# SCH_Esp32-LED-board_2025-09-09.net
KiCad netlist of a schematic drawn in EasyEDA
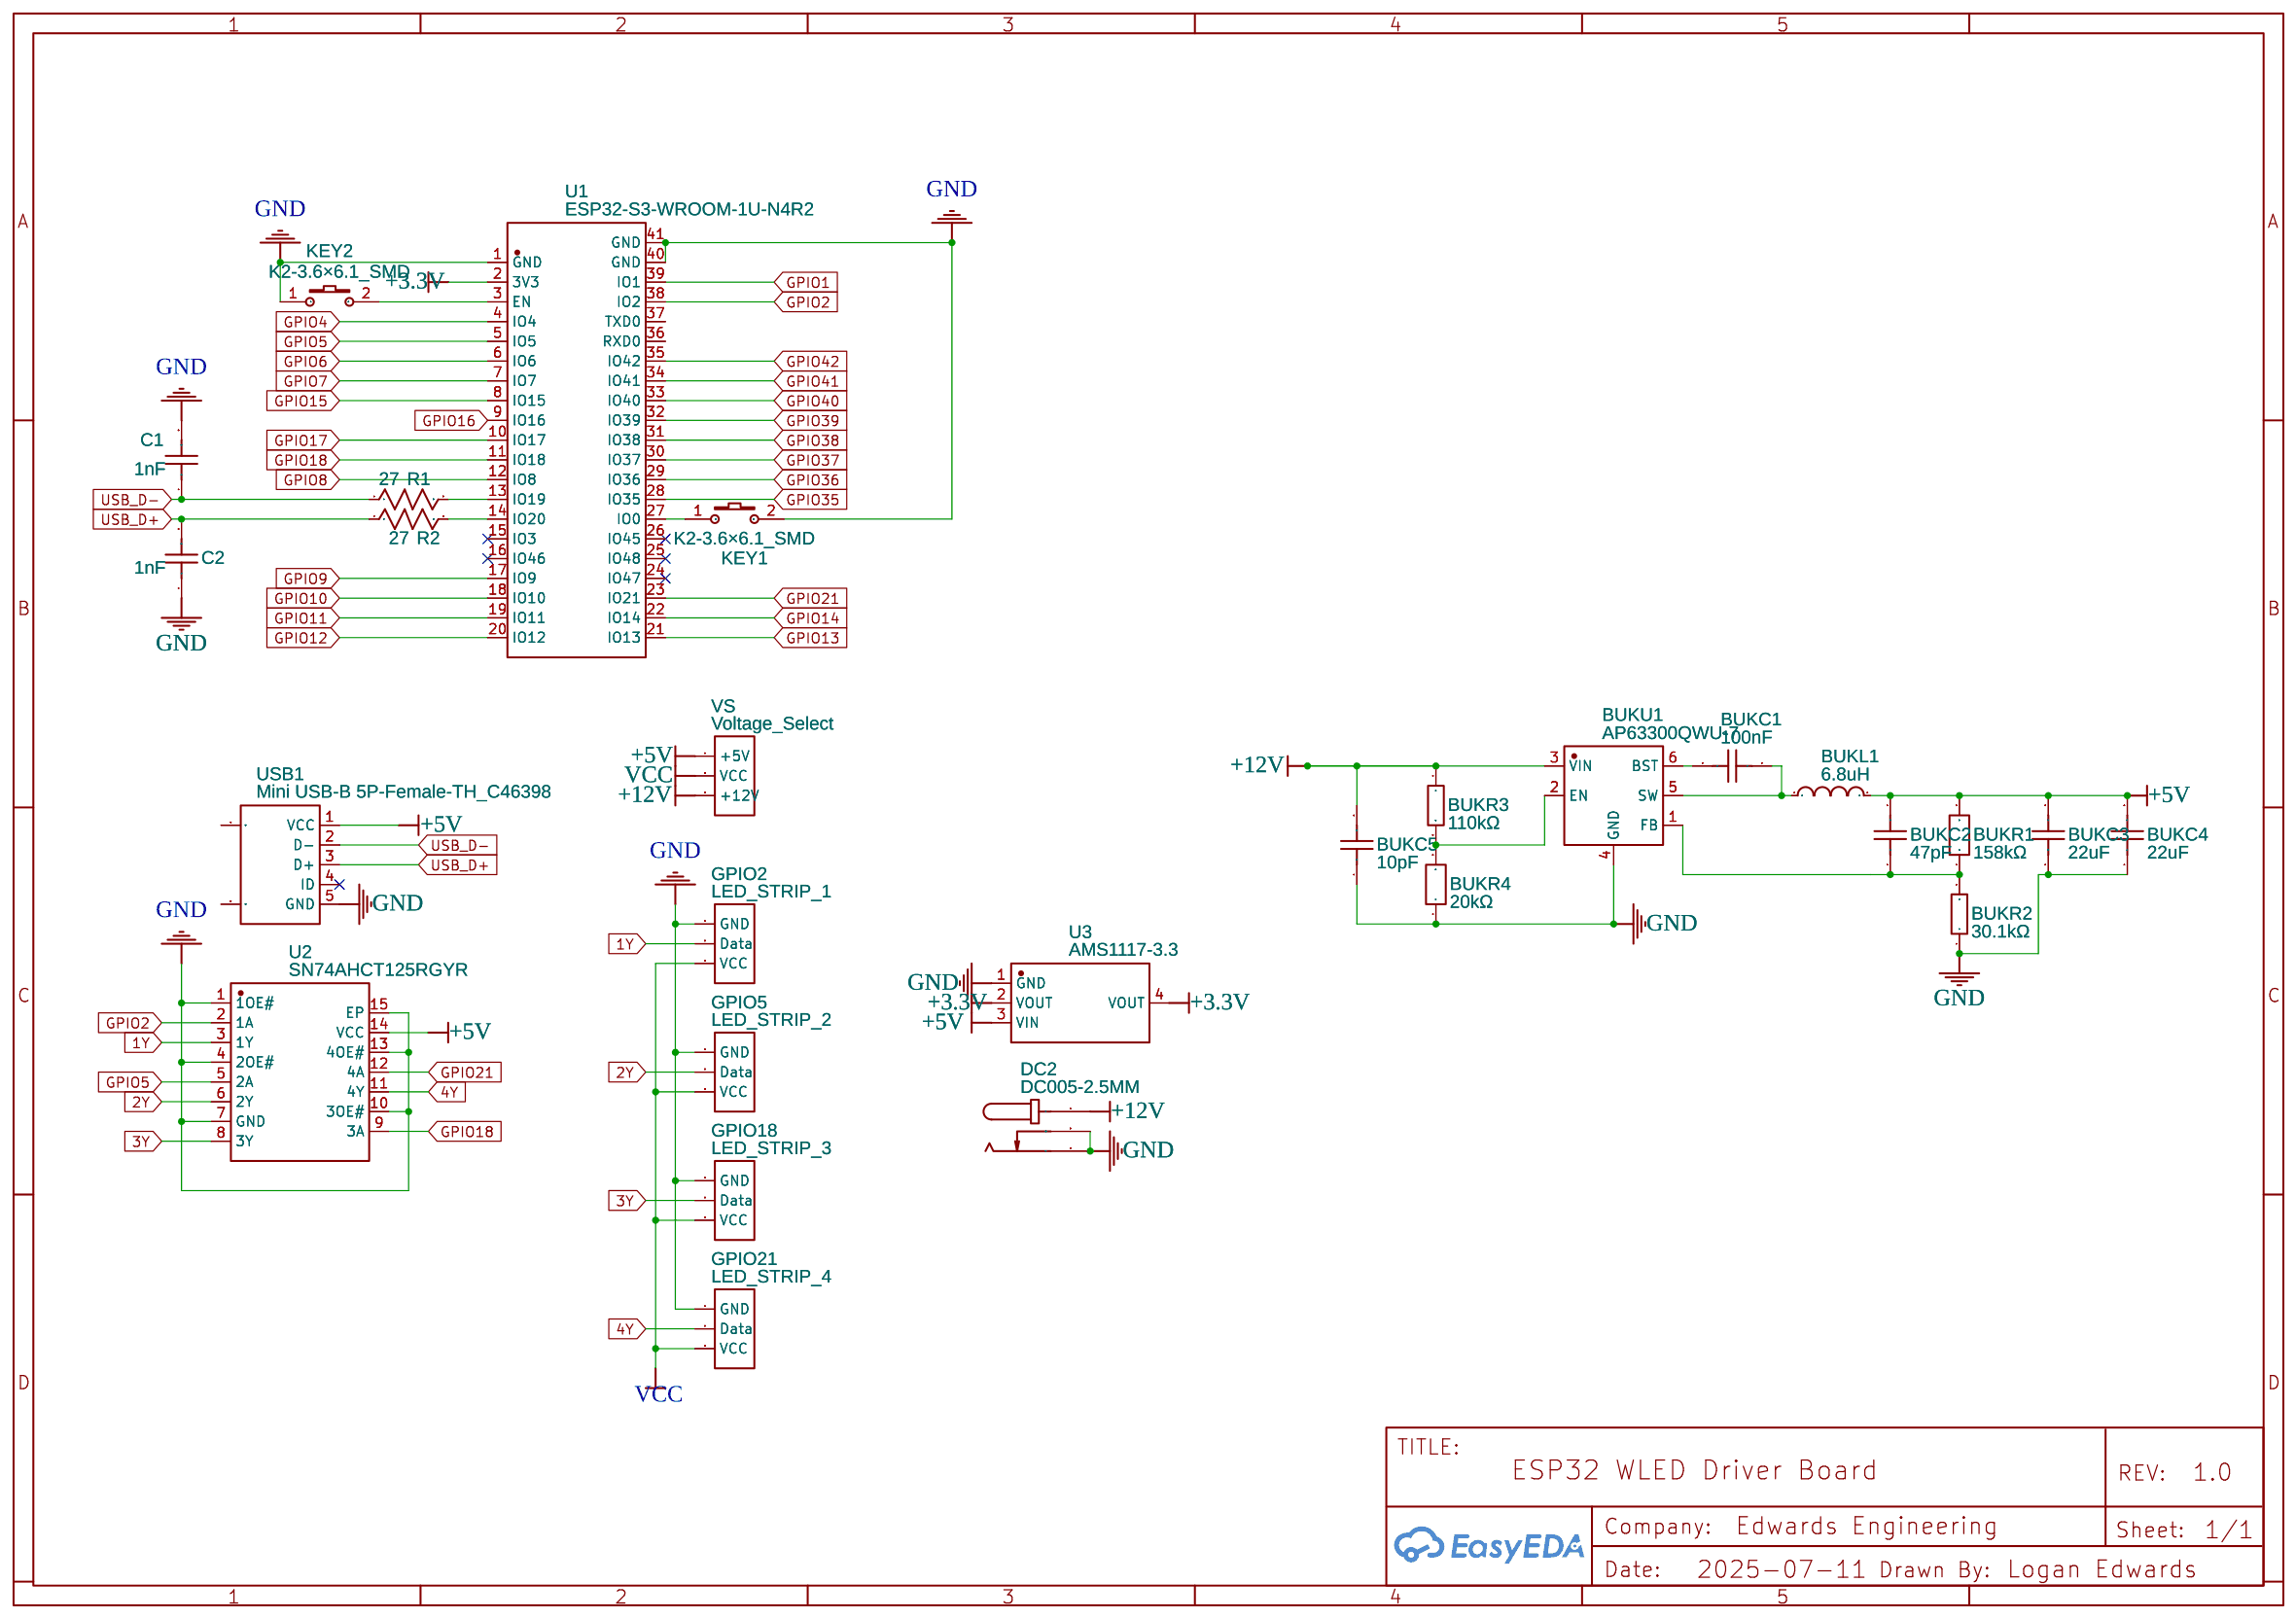
[diagram p0: schematic sheet]

(export (version "E")
  (design (tool "Eeschema 10.0.6"))
  (components
    (comp (ref "BUKC1")
      (value "100nF")
      (fields (field (name "Manufacturer Part") "0603B104J250NT") (field (name "Manufacturer") "FH(风华)"))
      (libsource (lib "") (part "0603B104J250NT"))
    )
    (comp (ref "BUKC2")
      (value "47pF")
      (fields
        (field (name "Manufacturer Part") "0603C0G470J500NT")
        (field (name "Manufacturer") "AIDE(爱迪电容)")
      )
      (libsource (lib "") (part "0603C0G470J500NT"))
    )
    (comp (ref "BUKC3")
      (value "22uF")
      (fields
        (field (name "Manufacturer Part") "HGC0603R5226M160NTHJ")
        (field (name "Manufacturer") "Chinocera(华瓷)")
      )
      (libsource (lib "") (part "HGC0603R5226M160NTHJ"))
    )
    (comp (ref "BUKC4")
      (value "22uF")
      (fields
        (field (name "Manufacturer Part") "HGC0603R5226M160NTHJ")
        (field (name "Manufacturer") "Chinocera(华瓷)")
      )
      (libsource (lib "") (part "HGC0603R5226M160NTHJ"))
    )
    (comp (ref "BUKC5")
      (value "10pF")
      (fields
        (field (name "Manufacturer Part") "CC0603FRNPO0BN100")
        (field (name "Manufacturer") "YAGEO(国巨)")
      )
      (libsource (lib "") (part "CC0603FRNPO0BN100"))
    )
    (comp (ref "BUKL1")
      (value "6.8uH")
      (fields (field (name "Manufacturer Part") "CMP160808JE6R8MT") (field (name "Manufacturer") "FH(风华)"))
      (libsource (lib "") (part "CMP160808JE6R8MT"))
    )
    (comp (ref "BUKR1")
      (value "158kΩ")
      (fields (field (name "Manufacturer Part") "FRC0603F1583TS") (field (name "Manufacturer") "FOJAN(富捷)"))
      (libsource (lib "") (part "FRC0603F1583TS"))
    )
    (comp (ref "BUKR2")
      (value "30.1kΩ")
      (fields
        (field (name "Manufacturer Part") "RMC060330.1K1%N")
        (field (name "Manufacturer") "Tyohm(幸亚电阻)")
      )
      (libsource (lib "") (part "RMC060330.1K1%N"))
    )
    (comp (ref "BUKR3")
      (value "110kΩ")
      (fields (field (name "Manufacturer Part") "RT0603BRD07110KL") (field (name "Manufacturer") "YAGEO(国巨)"))
      (libsource (lib "") (part "RT0603BRD07110KL"))
    )
    (comp (ref "BUKR4")
      (value "20kΩ")
      (fields (field (name "Manufacturer Part") "RT0603CRE0720KL") (field (name "Manufacturer") "YAGEO(国巨)"))
      (libsource (lib "") (part "RT0603CRE0720KL"))
    )
    (comp (ref "BUKU1")
      (value "AP63300QWU-7")
      (fields (field (name "Manufacturer") "DIODES(美台)"))
      (libsource (lib "") (part "AP63300QWU-7"))
    )
    (comp (ref "C1")
      (value "1nF")
      (fields
        (field (name "Manufacturer Part") "CL10B102KB8NNNC")
        (field (name "Manufacturer") "Samsung Electro-Mechanics")
      )
      (libsource (lib "") (part "C_0603_US"))
    )
    (comp (ref "C2")
      (value "1nF")
      (fields
        (field (name "Manufacturer Part") "CL10B102KB8NNNC")
        (field (name "Manufacturer") "Samsung Electro-Mechanics")
      )
      (libsource (lib "") (part "C_0603_US"))
    )
    (comp (ref "DC2")
      (value "DC005-2.5MM")
      (fields (field (name "Manufacturer Part") "DC005-T25") (field (name "Manufacturer") "SOFNG(硕方)"))
      (libsource (lib "") (part "DC005-2.5MM"))
    )
    (comp (ref "GPIO2")
      (value "LED_STRIP_1")
      (fields (field (name "Manufacturer Part") "2.54-1*3P针") (field (name "Manufacturer") "BOOMELE(博穆精密)"))
      (libsource (lib "") (part "Header-Male-2.54_1x3"))
    )
    (comp (ref "GPIO5")
      (value "LED_STRIP_2")
      (fields (field (name "Manufacturer Part") "2.54-1*3P针") (field (name "Manufacturer") "BOOMELE(博穆精密)"))
      (libsource (lib "") (part "Header-Male-2.54_1x3"))
    )
    (comp (ref "GPIO18")
      (value "LED_STRIP_3")
      (fields (field (name "Manufacturer Part") "2.54-1*3P针") (field (name "Manufacturer") "BOOMELE(博穆精密)"))
      (libsource (lib "") (part "Header-Male-2.54_1x3"))
    )
    (comp (ref "GPIO21")
      (value "LED_STRIP_4")
      (fields (field (name "Manufacturer Part") "2.54-1*3P针") (field (name "Manufacturer") "BOOMELE(博穆精密)"))
      (libsource (lib "") (part "Header-Male-2.54_1x3"))
    )
    (comp (ref "KEY1")
      (value "K2-3.6×6.1_SMD")
      (fields (field (name "Manufacturer Part") "K2-1107ST-A4SW-06"))
      (libsource (lib "") (part "K2-3.6×6.1_SMD"))
    )
    (comp (ref "KEY2")
      (value "K2-3.6×6.1_SMD")
      (fields (field (name "Manufacturer Part") "K2-1107ST-A4SW-06"))
      (libsource (lib "") (part "K2-3.6×6.1_SMD"))
    )
    (comp (ref "R1")
      (value "27")
      (fields
        (field (name "Manufacturer Part") "0603WAF270JT5E")
        (field (name "Manufacturer") "UNI-ROYAL(Uniroyal Elec)")
      )
      (libsource (lib "") (part "R_0603_US"))
    )
    (comp (ref "R2")
      (value "27")
      (fields
        (field (name "Manufacturer Part") "0603WAF270JT5E")
        (field (name "Manufacturer") "UNI-ROYAL(Uniroyal Elec)")
      )
      (libsource (lib "") (part "R_0603_US"))
    )
    (comp (ref "U1")
      (value "ESP32-S3-WROOM-1U-N4R2")
      (fields (field (name "Manufacturer") "ESPRESSIF(乐鑫)"))
      (libsource (lib "") (part "ESP32-S3-WROOM-1U-N4R2"))
    )
    (comp (ref "U2")
      (value "SN74AHCT125RGYR")
      (fields (field (name "Manufacturer") "TI(德州仪器)"))
      (libsource (lib "") (part "SN74AHCT125RGYR"))
    )
    (comp (ref "U3")
      (value "AMS1117-3.3")
      (fields (field (name "Manufacturer") "AMS"))
      (libsource (lib "") (part "AMS1117-3.3"))
    )
    (comp (ref "USB1")
      (value "Mini USB-B 5P-Female-TH_C46398")
      (fields (field (name "Manufacturer Part") "920-462A2021D10102") (field (name "Manufacturer") "精拓金"))
      (libsource (lib "") (part "Mini USB-B 5P-Female-TH_C46398"))
    )
    (comp (ref "VS")
      (value "Voltage_Select")
      (fields (field (name "Manufacturer Part") "2.54-1*3P针") (field (name "Manufacturer") "BOOMELE(博穆精密)"))
      (libsource (lib "") (part "Header-Male-2.54_1x3_1"))
    )
  )
  (nets
    (net (code "1") (name "+3.3V") (class "Default")
      (node (ref "U1") (pin "2") (pinfunction "3V3_2") (pintype "unspecified"))
      (node (ref "U3") (pin "2") (pinfunction "VOUT_2") (pintype "unspecified"))
      (node (ref "U3") (pin "4") (pinfunction "VOUT_4") (pintype "unspecified"))
    )
    (net (code "2") (name "+5V") (class "Default")
      (node (ref "BUKC2") (pin "2") (pinfunction "2_2") (pintype "unspecified"))
      (node (ref "BUKC3") (pin "2") (pinfunction "2_2") (pintype "unspecified"))
      (node (ref "BUKC4") (pin "2") (pinfunction "2_2") (pintype "unspecified"))
      (node (ref "BUKL1") (pin "2") (pinfunction "2_2") (pintype "unspecified"))
      (node (ref "BUKR1") (pin "2") (pinfunction "2_2") (pintype "unspecified"))
      (node (ref "U2") (pin "14") (pinfunction "VCC_14") (pintype "unspecified"))
      (node (ref "U3") (pin "3") (pinfunction "VIN_3") (pintype "unspecified"))
      (node (ref "USB1") (pin "1") (pinfunction "VCC_1") (pintype "input"))
      (node (ref "VS") (pin "1") (pinfunction "+5V_1") (pintype "input"))
    )
    (net (code "3") (name "+12V") (class "Default")
      (node (ref "BUKC5") (pin "2") (pinfunction "2_2") (pintype "unspecified"))
      (node (ref "BUKR3") (pin "1") (pinfunction "1_1") (pintype "unspecified"))
      (node (ref "BUKU1") (pin "3") (pinfunction "VIN_3") (pintype "unspecified"))
      (node (ref "DC2") (pin "1") (pinfunction "1_1") (pintype "unspecified"))
      (node (ref "VS") (pin "3") (pinfunction "+12V_3") (pintype "input"))
    )
    (net (code "4") (name "1Y") (class "Default")
      (node (ref "GPIO2") (pin "2") (pinfunction "Data_2") (pintype "input"))
      (node (ref "U2") (pin "3") (pinfunction "1Y_3") (pintype "unspecified"))
    )
    (net (code "5") (name "2Y") (class "Default")
      (node (ref "GPIO5") (pin "2") (pinfunction "Data_2") (pintype "input"))
      (node (ref "U2") (pin "6") (pinfunction "2Y_6") (pintype "unspecified"))
    )
    (net (code "6") (name "3Y") (class "Default")
      (node (ref "GPIO18") (pin "2") (pinfunction "Data_2") (pintype "input"))
      (node (ref "U2") (pin "8") (pinfunction "3Y_8") (pintype "unspecified"))
    )
    (net (code "7") (name "4Y") (class "Default")
      (node (ref "GPIO21") (pin "2") (pinfunction "Data_2") (pintype "input"))
      (node (ref "U2") (pin "11") (pinfunction "4Y_11") (pintype "unspecified"))
    )
    (net (code "8") (name "GND") (class "Default")
      (node (ref "BUKC3") (pin "1") (pinfunction "1_1") (pintype "unspecified"))
      (node (ref "BUKC4") (pin "1") (pinfunction "1_1") (pintype "unspecified"))
      (node (ref "BUKC5") (pin "1") (pinfunction "1_1") (pintype "unspecified"))
      (node (ref "BUKR2") (pin "1") (pinfunction "1_1") (pintype "unspecified"))
      (node (ref "BUKR4") (pin "1") (pinfunction "1_1") (pintype "unspecified"))
      (node (ref "BUKU1") (pin "4") (pinfunction "GND_4") (pintype "unspecified"))
      (node (ref "C1") (pin "2") (pinfunction "2_2") (pintype "unspecified"))
      (node (ref "C2") (pin "1") (pinfunction "1_1") (pintype "unspecified"))
      (node (ref "DC2") (pin "2") (pinfunction "2_2") (pintype "unspecified"))
      (node (ref "DC2") (pin "3") (pinfunction "3_3") (pintype "unspecified"))
      (node (ref "GPIO18") (pin "1") (pinfunction "GND_1") (pintype "input"))
      (node (ref "GPIO2") (pin "1") (pinfunction "GND_1") (pintype "input"))
      (node (ref "GPIO21") (pin "1") (pinfunction "GND_1") (pintype "input"))
      (node (ref "GPIO5") (pin "1") (pinfunction "GND_1") (pintype "input"))
      (node (ref "KEY1") (pin "2") (pinfunction "2_2") (pintype "unspecified"))
      (node (ref "KEY2") (pin "1") (pinfunction "1_1") (pintype "unspecified"))
      (node (ref "U1") (pin "1") (pinfunction "GND_1") (pintype "unspecified"))
      (node (ref "U1") (pin "40") (pinfunction "GND_40") (pintype "unspecified"))
      (node (ref "U1") (pin "41") (pinfunction "GND_41") (pintype "unspecified"))
      (node (ref "U2") (pin "1") (pinfunction "1OE#_1") (pintype "unspecified"))
      (node (ref "U2") (pin "10") (pinfunction "3OE#_10") (pintype "unspecified"))
      (node (ref "U2") (pin "13") (pinfunction "4OE#_13") (pintype "unspecified"))
      (node (ref "U2") (pin "15") (pinfunction "EP_15") (pintype "unspecified"))
      (node (ref "U2") (pin "4") (pinfunction "2OE#_4") (pintype "unspecified"))
      (node (ref "U2") (pin "7") (pinfunction "GND_7") (pintype "unspecified"))
      (node (ref "U3") (pin "1") (pinfunction "GND_1") (pintype "unspecified"))
      (node (ref "USB1") (pin "5") (pinfunction "GND_5") (pintype "input"))
    )
    (net (code "9") (name "GPIO1") (class "Default")
      (node (ref "U1") (pin "39") (pinfunction "IO1_39") (pintype "unspecified"))
    )
    (net (code "10") (name "GPIO2") (class "Default")
      (node (ref "U1") (pin "38") (pinfunction "IO2_38") (pintype "unspecified"))
      (node (ref "U2") (pin "2") (pinfunction "1A_2") (pintype "unspecified"))
    )
    (net (code "11") (name "GPIO4") (class "Default")
      (node (ref "U1") (pin "4") (pinfunction "IO4_4") (pintype "unspecified"))
    )
    (net (code "12") (name "GPIO5") (class "Default")
      (node (ref "U1") (pin "5") (pinfunction "IO5_5") (pintype "unspecified"))
      (node (ref "U2") (pin "5") (pinfunction "2A_5") (pintype "unspecified"))
    )
    (net (code "13") (name "GPIO6") (class "Default")
      (node (ref "U1") (pin "6") (pinfunction "IO6_6") (pintype "unspecified"))
    )
    (net (code "14") (name "GPIO7") (class "Default")
      (node (ref "U1") (pin "7") (pinfunction "IO7_7") (pintype "unspecified"))
    )
    (net (code "15") (name "GPIO8") (class "Default")
      (node (ref "U1") (pin "12") (pinfunction "IO8_12") (pintype "unspecified"))
    )
    (net (code "16") (name "GPIO9") (class "Default")
      (node (ref "U1") (pin "17") (pinfunction "IO9_17") (pintype "unspecified"))
    )
    (net (code "17") (name "GPIO10") (class "Default")
      (node (ref "U1") (pin "18") (pinfunction "IO10_18") (pintype "unspecified"))
    )
    (net (code "18") (name "GPIO11") (class "Default")
      (node (ref "U1") (pin "19") (pinfunction "IO11_19") (pintype "unspecified"))
    )
    (net (code "19") (name "GPIO12") (class "Default")
      (node (ref "U1") (pin "20") (pinfunction "IO12_20") (pintype "unspecified"))
    )
    (net (code "20") (name "GPIO13") (class "Default")
      (node (ref "U1") (pin "21") (pinfunction "IO13_21") (pintype "unspecified"))
    )
    (net (code "21") (name "GPIO14") (class "Default")
      (node (ref "U1") (pin "22") (pinfunction "IO14_22") (pintype "unspecified"))
    )
    (net (code "22") (name "GPIO15") (class "Default")
      (node (ref "U1") (pin "8") (pinfunction "IO15_8") (pintype "unspecified"))
    )
    (net (code "23") (name "GPIO16") (class "Default")
      (node (ref "U1") (pin "9") (pinfunction "IO16_9") (pintype "unspecified"))
    )
    (net (code "24") (name "GPIO17") (class "Default")
      (node (ref "U1") (pin "10") (pinfunction "IO17_10") (pintype "unspecified"))
    )
    (net (code "25") (name "GPIO18") (class "Default")
      (node (ref "U1") (pin "11") (pinfunction "IO18_11") (pintype "unspecified"))
      (node (ref "U2") (pin "9") (pinfunction "3A_9") (pintype "unspecified"))
    )
    (net (code "26") (name "GPIO21") (class "Default")
      (node (ref "U1") (pin "23") (pinfunction "IO21_23") (pintype "unspecified"))
      (node (ref "U2") (pin "12") (pinfunction "4A_12") (pintype "unspecified"))
    )
    (net (code "27") (name "GPIO35") (class "Default")
      (node (ref "U1") (pin "28") (pinfunction "IO35_28") (pintype "unspecified"))
    )
    (net (code "28") (name "GPIO36") (class "Default")
      (node (ref "U1") (pin "29") (pinfunction "IO36_29") (pintype "unspecified"))
    )
    (net (code "29") (name "GPIO37") (class "Default")
      (node (ref "U1") (pin "30") (pinfunction "IO37_30") (pintype "unspecified"))
    )
    (net (code "30") (name "GPIO38") (class "Default")
      (node (ref "U1") (pin "31") (pinfunction "IO38_31") (pintype "unspecified"))
    )
    (net (code "31") (name "GPIO39") (class "Default")
      (node (ref "U1") (pin "32") (pinfunction "IO39_32") (pintype "unspecified"))
    )
    (net (code "32") (name "GPIO40") (class "Default")
      (node (ref "U1") (pin "33") (pinfunction "IO40_33") (pintype "unspecified"))
    )
    (net (code "33") (name "GPIO41") (class "Default")
      (node (ref "U1") (pin "34") (pinfunction "IO41_34") (pintype "unspecified"))
    )
    (net (code "34") (name "GPIO42") (class "Default")
      (node (ref "U1") (pin "35") (pinfunction "IO42_35") (pintype "unspecified"))
    )
    (net (code "35") (name "Net-(BUKU1-BST)") (class "Default")
      (node (ref "BUKC1") (pin "1") (pinfunction "1_1") (pintype "unspecified"))
      (node (ref "BUKU1") (pin "6") (pinfunction "BST_6") (pintype "unspecified"))
    )
    (net (code "36") (name "Net-(BUKU1-EN)") (class "Default")
      (node (ref "BUKR3") (pin "2") (pinfunction "2_2") (pintype "unspecified"))
      (node (ref "BUKR4") (pin "2") (pinfunction "2_2") (pintype "unspecified"))
      (node (ref "BUKU1") (pin "2") (pinfunction "EN_2") (pintype "unspecified"))
    )
    (net (code "37") (name "Net-(BUKU1-FB)") (class "Default")
      (node (ref "BUKC2") (pin "1") (pinfunction "1_1") (pintype "unspecified"))
      (node (ref "BUKR1") (pin "1") (pinfunction "1_1") (pintype "unspecified"))
      (node (ref "BUKR2") (pin "2") (pinfunction "2_2") (pintype "unspecified"))
      (node (ref "BUKU1") (pin "1") (pinfunction "FB_1") (pintype "unspecified"))
    )
    (net (code "38") (name "Net-(BUKU1-SW)") (class "Default")
      (node (ref "BUKC1") (pin "2") (pinfunction "2_2") (pintype "unspecified"))
      (node (ref "BUKL1") (pin "1") (pinfunction "1_1") (pintype "unspecified"))
      (node (ref "BUKU1") (pin "5") (pinfunction "SW_5") (pintype "unspecified"))
    )
    (net (code "39") (name "Net-(U1-EN)") (class "Default")
      (node (ref "KEY2") (pin "2") (pinfunction "2_2") (pintype "unspecified"))
      (node (ref "U1") (pin "3") (pinfunction "EN_3") (pintype "unspecified"))
    )
    (net (code "40") (name "Net-(U1-IO0)") (class "Default")
      (node (ref "KEY1") (pin "1") (pinfunction "1_1") (pintype "unspecified"))
      (node (ref "U1") (pin "27") (pinfunction "IO0_27") (pintype "unspecified"))
    )
    (net (code "41") (name "Net-(U1-IO19)") (class "Default")
      (node (ref "R1") (pin "2") (pinfunction "2_2") (pintype "unspecified"))
      (node (ref "U1") (pin "13") (pinfunction "IO19_13") (pintype "unspecified"))
    )
    (net (code "42") (name "Net-(U1-IO20)") (class "Default")
      (node (ref "R2") (pin "2") (pinfunction "2_2") (pintype "unspecified"))
      (node (ref "U1") (pin "14") (pinfunction "IO20_14") (pintype "unspecified"))
    )
    (net (code "43") (name "USB_D+") (class "Default")
      (node (ref "C2") (pin "2") (pinfunction "2_2") (pintype "unspecified"))
      (node (ref "R2") (pin "1") (pinfunction "1_1") (pintype "unspecified"))
      (node (ref "USB1") (pin "3") (pinfunction "D+_3") (pintype "input"))
    )
    (net (code "44") (name "USB_D-") (class "Default")
      (node (ref "C1") (pin "1") (pinfunction "1_1") (pintype "unspecified"))
      (node (ref "R1") (pin "1") (pinfunction "1_1") (pintype "unspecified"))
      (node (ref "USB1") (pin "2") (pinfunction "D-_2") (pintype "input"))
    )
    (net (code "45") (name "VCC") (class "Default")
      (node (ref "GPIO18") (pin "3") (pinfunction "VCC_3") (pintype "input"))
      (node (ref "GPIO2") (pin "3") (pinfunction "VCC_3") (pintype "input"))
      (node (ref "GPIO21") (pin "3") (pinfunction "VCC_3") (pintype "input"))
      (node (ref "GPIO5") (pin "3") (pinfunction "VCC_3") (pintype "input"))
      (node (ref "VS") (pin "2") (pinfunction "VCC_2") (pintype "input"))
    )
    (net (code "46") (name "unconnected-(U1-IO3-Pad15)") (class "Default")
      (node (ref "U1") (pin "15") (pinfunction "IO3_15") (pintype "unspecified+no_connect"))
    )
    (net (code "47") (name "unconnected-(U1-IO45-Pad26)") (class "Default")
      (node (ref "U1") (pin "26") (pinfunction "IO45_26") (pintype "unspecified+no_connect"))
    )
    (net (code "48") (name "unconnected-(U1-IO46-Pad16)") (class "Default")
      (node (ref "U1") (pin "16") (pinfunction "IO46_16") (pintype "unspecified+no_connect"))
    )
    (net (code "49") (name "unconnected-(U1-IO47-Pad24)") (class "Default")
      (node (ref "U1") (pin "24") (pinfunction "IO47_24") (pintype "unspecified+no_connect"))
    )
    (net (code "50") (name "unconnected-(U1-IO48-Pad25)") (class "Default")
      (node (ref "U1") (pin "25") (pinfunction "IO48_25") (pintype "unspecified+no_connect"))
    )
    (net (code "51") (name "unconnected-(U1-RXD0-Pad36)") (class "Default")
      (node (ref "U1") (pin "36") (pinfunction "RXD0_36") (pintype "unspecified"))
    )
    (net (code "52") (name "unconnected-(U1-TXD0-Pad37)") (class "Default")
      (node (ref "U1") (pin "37") (pinfunction "TXD0_37") (pintype "unspecified"))
    )
    (net (code "53") (name "unconnected-(USB1-ID-Pad4)") (class "Default")
      (node (ref "USB1") (pin "4") (pinfunction "ID_4") (pintype "input+no_connect"))
    )
    (net (code "54") (name "unconnected-(USB1-Pad0)") (class "Default")
      (node (ref "USB1") (pin "0") (pinfunction "0_0") (pintype "unspecified"))
    )
    (net (code "55") (name "unconnected-(USB1-Pad0)_1") (class "Default")
      (node (ref "USB1") (pin "0") (pinfunction "0_0") (pintype "unspecified"))
    )
  )
)
